# ique_xbox_flex_r1.net
KiCad netlist of a schematic drawn in EasyEDA Pro
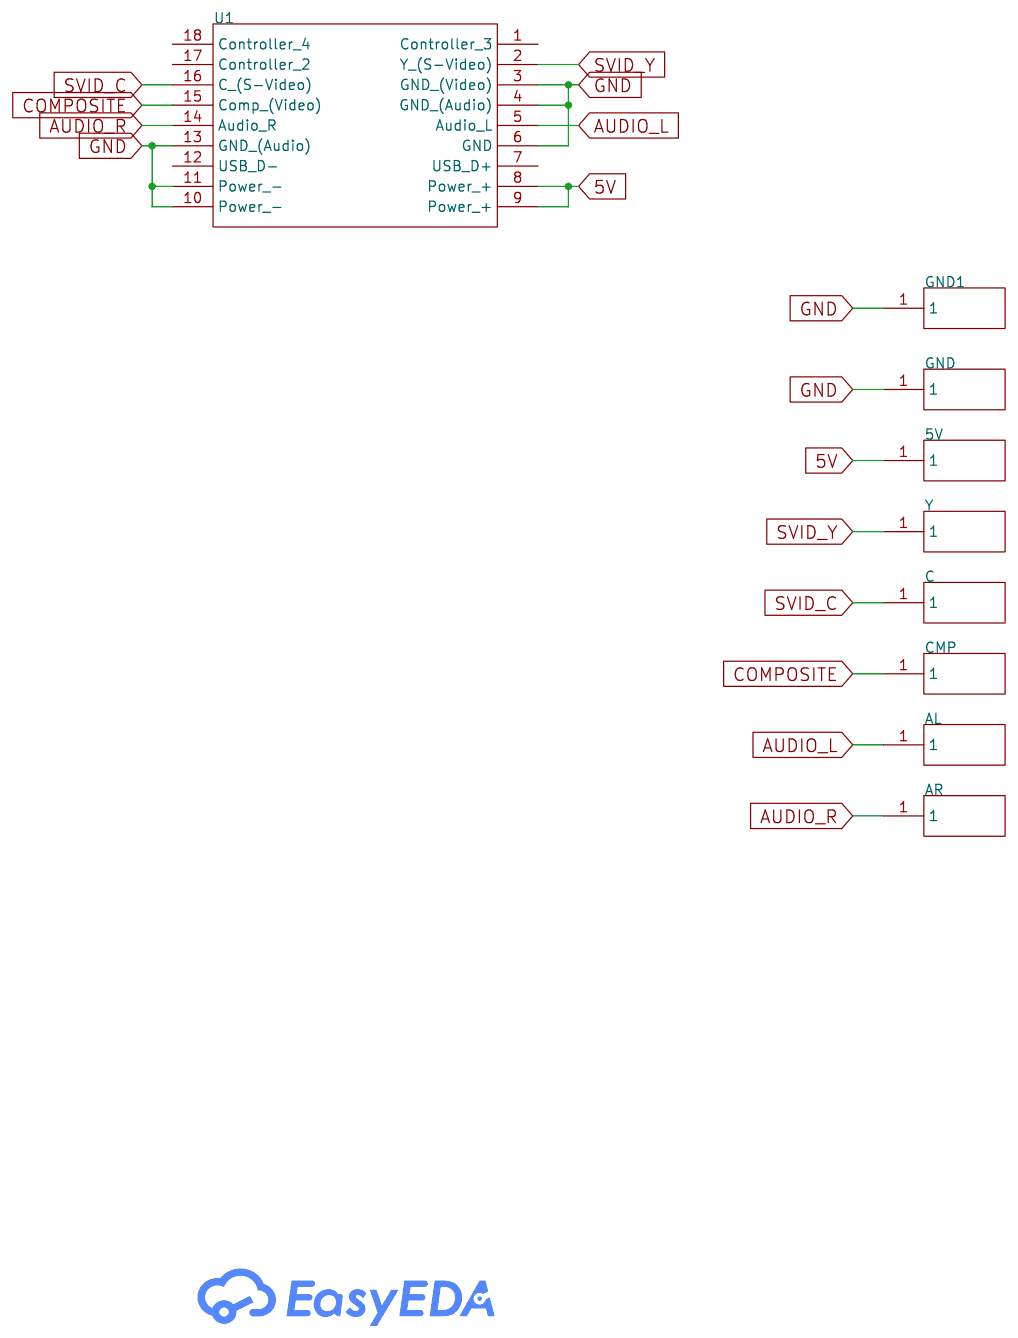
[diagram p0: schematic sheet]

(export (version "E")
  (design (tool "Eeschema 10.0.6"))
  (components
    (comp (ref "5V")
      (value "~")
      (footprint "easyedapro:sqpad_3mm")
      (libsource (lib "easyedapro") (part "sqpad_3mm"))
    )
    (comp (ref "AL")
      (value "~")
      (footprint "easyedapro:sqpad_3mm")
      (libsource (lib "easyedapro") (part "sqpad_3mm"))
    )
    (comp (ref "AR")
      (value "~")
      (footprint "easyedapro:sqpad_3mm")
      (libsource (lib "easyedapro") (part "sqpad_3mm"))
    )
    (comp (ref "C")
      (value "~")
      (footprint "easyedapro:sqpad_3mm")
      (libsource (lib "easyedapro") (part "sqpad_3mm"))
    )
    (comp (ref "CMP")
      (value "~")
      (footprint "easyedapro:sqpad_3mm")
      (libsource (lib "easyedapro") (part "sqpad_3mm"))
    )
    (comp (ref "GND")
      (value "~")
      (footprint "easyedapro:sqpad_3mm")
      (libsource (lib "easyedapro") (part "sqpad_3mm"))
    )
    (comp (ref "GND1")
      (value "~")
      (footprint "easyedapro:sqpad_3mm")
      (libsource (lib "easyedapro") (part "sqpad_3mm"))
    )
    (comp (ref "U1")
      (value "~")
      (footprint "easyedapro:iQue_Connector_Flex")
      (libsource (lib "easyedapro") (part "ique_connector_flex"))
    )
    (comp (ref "Y")
      (value "~")
      (footprint "easyedapro:sqpad_3mm")
      (libsource (lib "easyedapro") (part "sqpad_3mm"))
    )
  )
  (nets
    (net (code "1") (name "5V") (class "Default")
      (node (ref "5V") (pin "1") (pinfunction "1_1") (pintype "input"))
      (node (ref "U1") (pin "8") (pinfunction "Power_+_8") (pintype "input"))
      (node (ref "U1") (pin "9") (pinfunction "Power_+_9") (pintype "input"))
    )
    (net (code "2") (name "AUDIO_L") (class "Default")
      (node (ref "AL") (pin "1") (pinfunction "1_1") (pintype "input"))
      (node (ref "U1") (pin "5") (pinfunction "Audio_L_5") (pintype "input"))
    )
    (net (code "3") (name "AUDIO_R") (class "Default")
      (node (ref "AR") (pin "1") (pinfunction "1_1") (pintype "input"))
      (node (ref "U1") (pin "14") (pinfunction "Audio_R_14") (pintype "input"))
    )
    (net (code "4") (name "COMPOSITE") (class "Default")
      (node (ref "CMP") (pin "1") (pinfunction "1_1") (pintype "input"))
      (node (ref "U1") (pin "15") (pinfunction "Comp_(Video)_15") (pintype "input"))
    )
    (net (code "5") (name "GND") (class "Default")
      (node (ref "GND") (pin "1") (pinfunction "1_1") (pintype "input"))
      (node (ref "GND1") (pin "1") (pinfunction "1_1") (pintype "input"))
      (node (ref "U1") (pin "10") (pinfunction "Power_-_10") (pintype "input"))
      (node (ref "U1") (pin "11") (pinfunction "Power_-_11") (pintype "input"))
      (node (ref "U1") (pin "13") (pinfunction "GND_(Audio)_13") (pintype "input"))
      (node (ref "U1") (pin "3") (pinfunction "GND_(Video)_3") (pintype "input"))
      (node (ref "U1") (pin "4") (pinfunction "GND_(Audio)_4") (pintype "input"))
      (node (ref "U1") (pin "6") (pinfunction "GND_6") (pintype "input"))
    )
    (net (code "6") (name "SVID_C") (class "Default")
      (node (ref "C") (pin "1") (pinfunction "1_1") (pintype "input"))
      (node (ref "U1") (pin "16") (pinfunction "C_(S-Video)_16") (pintype "input"))
    )
    (net (code "7") (name "SVID_Y") (class "Default")
      (node (ref "U1") (pin "2") (pinfunction "Y_(S-Video)_2") (pintype "input"))
      (node (ref "Y") (pin "1") (pinfunction "1_1") (pintype "input"))
    )
    (net (code "8") (name "unconnected-(U1-Controller_2-Pad17)") (class "Default")
      (node (ref "U1") (pin "17") (pinfunction "Controller_2_17") (pintype "input"))
    )
    (net (code "9") (name "unconnected-(U1-Controller_3-Pad1)") (class "Default")
      (node (ref "U1") (pin "1") (pinfunction "Controller_3_1") (pintype "input"))
    )
    (net (code "10") (name "unconnected-(U1-Controller_4-Pad18)") (class "Default")
      (node (ref "U1") (pin "18") (pinfunction "Controller_4_18") (pintype "input"))
    )
    (net (code "11") (name "unconnected-(U1-USB_D+-Pad7)") (class "Default")
      (node (ref "U1") (pin "7") (pinfunction "USB_D+_7") (pintype "input"))
    )
    (net (code "12") (name "unconnected-(U1-USB_D--Pad12)") (class "Default")
      (node (ref "U1") (pin "12") (pinfunction "USB_D-_12") (pintype "input"))
    )
  )
)
